# Controller.net
KiCad netlist of a schematic drawn in Altium Designer
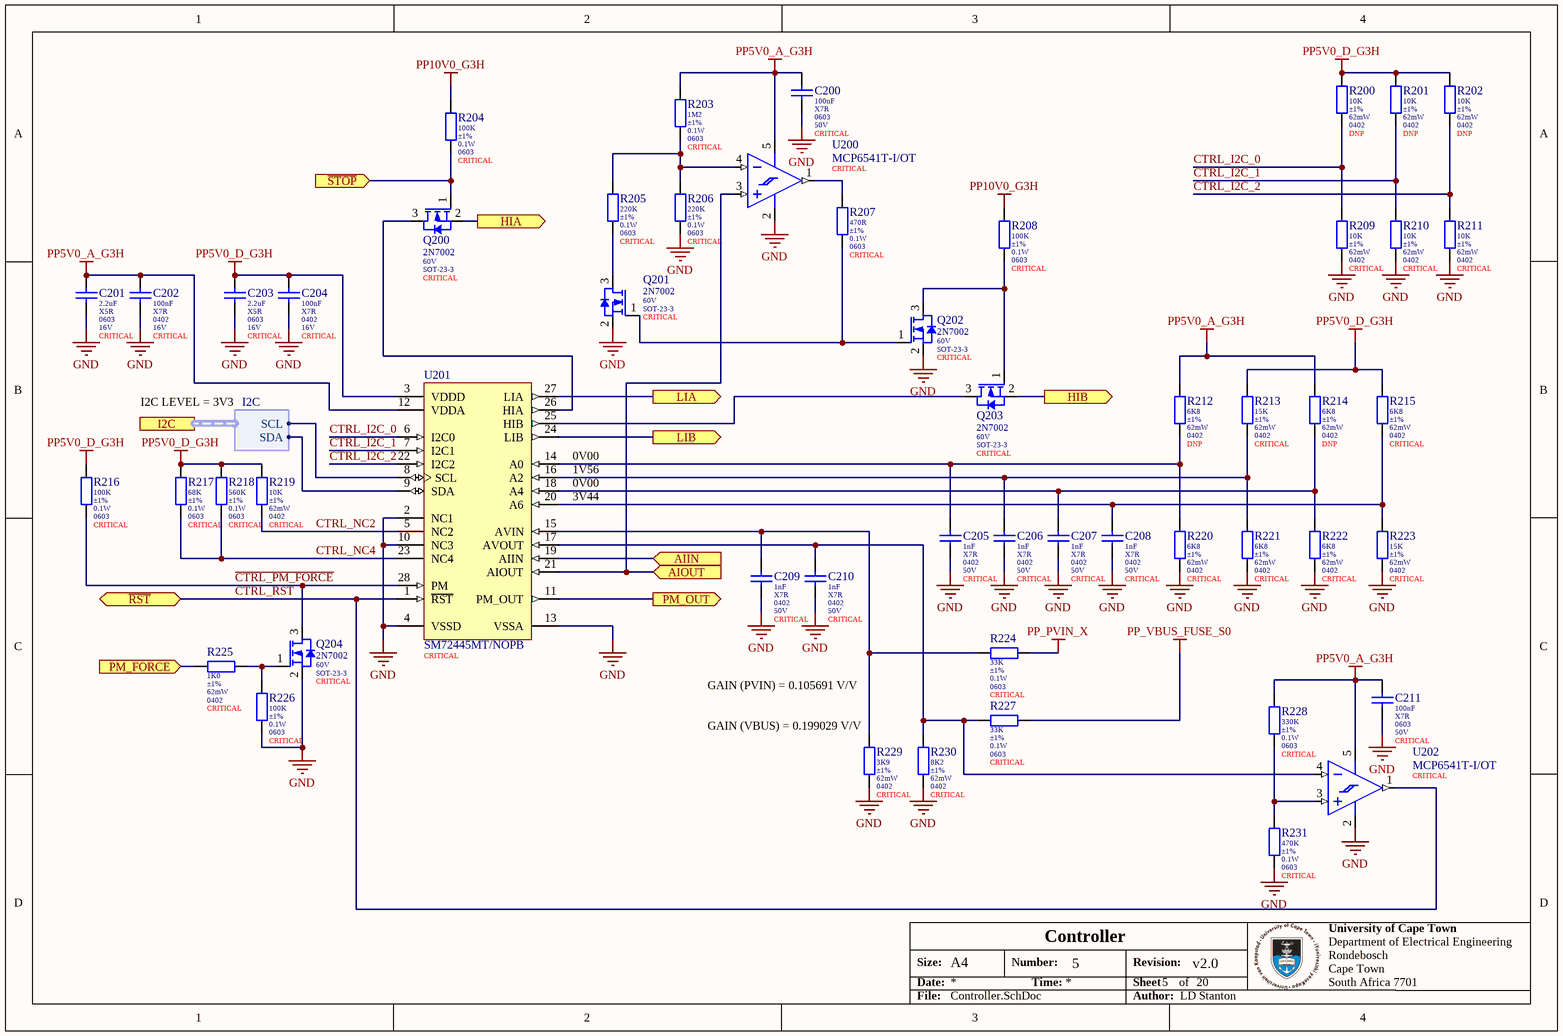
[diagram p0: Controller.SchDoc]

(export (version "E")
  (design (tool "Eeschema 10.0.6"))
  (components
    (comp (ref "C200")
      (value "100nF")
      (footprint "0603 (Yageo DA) B")
      (description "MLCC 100nF 50V 0603 X7R ±10%")
      (fields
        (field (name "DIELECTRIC") "X7R")
        (field (name "PACKAGE") "0603")
        (field (name "VOLTAGE") "50V")
        (field (name "POPULATE") "CRITICAL")
        (field (name "LCSC PART NUMBER") "C14663")
        (field (name "TOLERANCE") "±10%")
      )
      (libsource (lib "University of Cape Town") (part "Symbol"))
    )
    (comp (ref "C201")
      (value "2.2uF")
      (footprint "0603_080_8 (Samsung) B")
      (description "MLCC 2.2uF 0603 16V X5R ±10%")
      (fields
        (field (name "DIELECTRIC") "X5R")
        (field (name "PACKAGE") "0603")
        (field (name "VOLTAGE") "16V")
        (field (name "POPULATE") "CRITICAL")
        (field (name "MANUFACTURER") "Samsung")
        (field (name "LCSC PART NUMBER") "C23630")
      )
      (libsource (lib "University of Cape Town") (part "Symbol"))
    )
    (comp (ref "C202")
      (value "100nF")
      (footprint "0402_050_5 (Samsumg) B")
      (description "MLCC 100nF 0402 16V X7R ±10%")
      (fields
        (field (name "DIELECTRIC") "X7R")
        (field (name "PACKAGE") "0402")
        (field (name "VOLTAGE") "16V")
        (field (name "POPULATE") "CRITICAL")
        (field (name "TOLERANCE") "±10%")
        (field (name "LCSC PART NUMBER") "C1525")
      )
      (libsource (lib "University of Cape Town") (part "Symbol"))
    )
    (comp (ref "C203")
      (value "2.2uF")
      (footprint "0603_080_8 (Samsung) B")
      (description "MLCC 2.2uF 0603 16V X5R ±10%")
      (fields
        (field (name "DIELECTRIC") "X5R")
        (field (name "PACKAGE") "0603")
        (field (name "VOLTAGE") "16V")
        (field (name "POPULATE") "CRITICAL")
        (field (name "MANUFACTURER") "Samsung")
        (field (name "LCSC PART NUMBER") "C23630")
      )
      (libsource (lib "University of Cape Town") (part "Symbol"))
    )
    (comp (ref "C204")
      (value "100nF")
      (footprint "0402_050_5 (Samsumg) B")
      (description "MLCC 100nF 0402 16V X7R ±10%")
      (fields
        (field (name "DIELECTRIC") "X7R")
        (field (name "PACKAGE") "0402")
        (field (name "VOLTAGE") "16V")
        (field (name "POPULATE") "CRITICAL")
        (field (name "TOLERANCE") "±10%")
        (field (name "LCSC PART NUMBER") "C1525")
      )
      (libsource (lib "University of Cape Town") (part "Symbol"))
    )
    (comp (ref "C205")
      (value "1nF")
      (footprint "0402_050 (Guandong) B")
      (description "MLCC 1nF 0402 50V X7R ±10%")
      (fields
        (field (name "DIELECTRIC") "X7R")
        (field (name "PACKAGE") "0402")
        (field (name "VOLTAGE") "50V")
        (field (name "POPULATE") "CRITICAL")
        (field (name "LCSC PART NUMBER") "C1523")
        (field (name "MANUFACTURER") "Guandong")
      )
      (libsource (lib "University of Cape Town") (part "Symbol"))
    )
    (comp (ref "C206")
      (value "1nF")
      (footprint "0402_050 (Guandong) B")
      (description "MLCC 1nF 0402 50V X7R ±10%")
      (fields
        (field (name "DIELECTRIC") "X7R")
        (field (name "PACKAGE") "0402")
        (field (name "VOLTAGE") "50V")
        (field (name "POPULATE") "CRITICAL")
        (field (name "LCSC PART NUMBER") "C1523")
        (field (name "MANUFACTURER") "Guandong")
      )
      (libsource (lib "University of Cape Town") (part "Symbol"))
    )
    (comp (ref "C207")
      (value "1nF")
      (footprint "0402_050 (Guandong) B")
      (description "MLCC 1nF 0402 50V X7R ±10%")
      (fields
        (field (name "DIELECTRIC") "X7R")
        (field (name "PACKAGE") "0402")
        (field (name "VOLTAGE") "50V")
        (field (name "POPULATE") "CRITICAL")
        (field (name "LCSC PART NUMBER") "C1523")
        (field (name "MANUFACTURER") "Guandong")
      )
      (libsource (lib "University of Cape Town") (part "Symbol"))
    )
    (comp (ref "C208")
      (value "1nF")
      (footprint "0402_050 (Guandong) B")
      (description "MLCC 1nF 0402 50V X7R ±10%")
      (fields
        (field (name "DIELECTRIC") "X7R")
        (field (name "PACKAGE") "0402")
        (field (name "VOLTAGE") "50V")
        (field (name "POPULATE") "CRITICAL")
        (field (name "LCSC PART NUMBER") "C1523")
        (field (name "MANUFACTURER") "Guandong")
      )
      (libsource (lib "University of Cape Town") (part "Symbol"))
    )
    (comp (ref "C209")
      (value "1nF")
      (footprint "0402_050 (Guandong) B")
      (description "MLCC 1nF 0402 50V X7R ±10%")
      (fields
        (field (name "DIELECTRIC") "X7R")
        (field (name "PACKAGE") "0402")
        (field (name "VOLTAGE") "50V")
        (field (name "POPULATE") "CRITICAL")
        (field (name "LCSC PART NUMBER") "C1523")
        (field (name "MANUFACTURER") "Guandong")
      )
      (libsource (lib "University of Cape Town") (part "Symbol"))
    )
    (comp (ref "C210")
      (value "1nF")
      (footprint "0402_050 (Guandong) B")
      (description "MLCC 1nF 0402 50V X7R ±10%")
      (fields
        (field (name "DIELECTRIC") "X7R")
        (field (name "PACKAGE") "0402")
        (field (name "VOLTAGE") "50V")
        (field (name "POPULATE") "CRITICAL")
        (field (name "LCSC PART NUMBER") "C1523")
        (field (name "MANUFACTURER") "Guandong")
      )
      (libsource (lib "University of Cape Town") (part "Symbol"))
    )
    (comp (ref "C211")
      (value "100nF")
      (footprint "0603 (Yageo DA) B")
      (description "MLCC 100nF 50V 0603 X7R ±10%")
      (fields
        (field (name "DIELECTRIC") "X7R")
        (field (name "PACKAGE") "0603")
        (field (name "VOLTAGE") "50V")
        (field (name "POPULATE") "CRITICAL")
        (field (name "LCSC PART NUMBER") "C14663")
        (field (name "TOLERANCE") "±10%")
      )
      (libsource (lib "University of Cape Town") (part "Symbol"))
    )
    (comp (ref "Q200")
      (value "2N7002")
      (footprint "SOT-23-3 (2N7002) B")
      (description "Small Signal MOSFET, 500 mA, 60 V, N-Channel, Enhancement, JCET SOT-23-3")
      (fields
        (field (name "MAXIMUM DRAIN SOURCE VOLTAGE") "60V")
        (field (name "PACKAGE") "SOT-23-3")
        (field (name "PLACEMENT") "CRITICAL")
        (field (name "POWER") "0.225W")
        (field (name "LCSC PART NUMBER") "C8545")
      )
      (libsource (lib "University of Cape Town") (part "N Channel Transistor SOT-23-3"))
    )
    (comp (ref "Q201")
      (value "2N7002")
      (footprint "SOT-23-3 (2N7002) B")
      (description "Small Signal MOSFET, 500 mA, 60 V, N-Channel, Enhancement, JCET SOT-23-3")
      (fields
        (field (name "MAXIMUM DRAIN SOURCE VOLTAGE") "60V")
        (field (name "PACKAGE") "SOT-23-3")
        (field (name "PLACEMENT") "CRITICAL")
        (field (name "POWER") "0.225W")
        (field (name "LCSC PART NUMBER") "C8545")
      )
      (libsource (lib "University of Cape Town") (part "N Channel Transistor SOT-23-3"))
    )
    (comp (ref "Q202")
      (value "2N7002")
      (footprint "SOT-23-3 (2N7002) B")
      (description "Small Signal MOSFET, 500 mA, 60 V, N-Channel, Enhancement, JCET SOT-23-3")
      (fields
        (field (name "MAXIMUM DRAIN SOURCE VOLTAGE") "60V")
        (field (name "PACKAGE") "SOT-23-3")
        (field (name "PLACEMENT") "CRITICAL")
        (field (name "POWER") "0.225W")
        (field (name "LCSC PART NUMBER") "C8545")
      )
      (libsource (lib "University of Cape Town") (part "N Channel Transistor SOT-23-3"))
    )
    (comp (ref "Q203")
      (value "2N7002")
      (footprint "SOT-23-3 (2N7002) B")
      (description "Small Signal MOSFET, 500 mA, 60 V, N-Channel, Enhancement, JCET SOT-23-3")
      (fields
        (field (name "MAXIMUM DRAIN SOURCE VOLTAGE") "60V")
        (field (name "PACKAGE") "SOT-23-3")
        (field (name "PLACEMENT") "CRITICAL")
        (field (name "POWER") "0.225W")
        (field (name "LCSC PART NUMBER") "C8545")
      )
      (libsource (lib "University of Cape Town") (part "N Channel Transistor SOT-23-3"))
    )
    (comp (ref "Q204")
      (value "2N7002")
      (footprint "SOT-23-3 (2N7002) B")
      (description "Small Signal MOSFET, 500 mA, 60 V, N-Channel, Enhancement, JCET SOT-23-3")
      (fields
        (field (name "MAXIMUM DRAIN SOURCE VOLTAGE") "60V")
        (field (name "PACKAGE") "SOT-23-3")
        (field (name "PLACEMENT") "CRITICAL")
        (field (name "POWER") "0.225W")
        (field (name "LCSC PART NUMBER") "C8545")
      )
      (libsource (lib "University of Cape Town") (part "N Channel Transistor SOT-23-3"))
    )
    (comp (ref "R200")
      (value "10K")
      (footprint "0402 (Uniroyal) B")
      (description "Resistor 10K 0402 ±1% Thick Film Uniroyal")
      (fields
        (field (name "TOLERANCE") "±1%")
        (field (name "POWER") "62mW")
        (field (name "PACKAGE") "0402")
        (field (name "POPULATE") "DNP")
        (field (name "MANUFACTURER") "Uniroyal")
        (field (name "LCSC PART NUMBER") "C25744")
      )
      (libsource (lib "University of Cape Town") (part "Chip Resistor"))
    )
    (comp (ref "R201")
      (value "10K")
      (footprint "0402 (Uniroyal) B")
      (description "Resistor 10K 0402 ±1% Thick Film Uniroyal")
      (fields
        (field (name "TOLERANCE") "±1%")
        (field (name "POWER") "62mW")
        (field (name "PACKAGE") "0402")
        (field (name "POPULATE") "DNP")
        (field (name "MANUFACTURER") "Uniroyal")
        (field (name "LCSC PART NUMBER") "C25744")
      )
      (libsource (lib "University of Cape Town") (part "Chip Resistor"))
    )
    (comp (ref "R202")
      (value "10K")
      (footprint "0402 (Uniroyal) B")
      (description "Resistor 10K 0402 ±1% Thick Film Uniroyal")
      (fields
        (field (name "TOLERANCE") "±1%")
        (field (name "POWER") "62mW")
        (field (name "PACKAGE") "0402")
        (field (name "POPULATE") "DNP")
        (field (name "MANUFACTURER") "Uniroyal")
        (field (name "LCSC PART NUMBER") "C25744")
      )
      (libsource (lib "University of Cape Town") (part "Chip Resistor"))
    )
    (comp (ref "R203")
      (value "1M2")
      (footprint "0603 (Uniroyal) B")
      (description "Resistor 1M2 0603 ±1% Thick Film Uniroyal")
      (fields
        (field (name "TOLERANCE") "±1%")
        (field (name "POWER") "0.1W")
        (field (name "PACKAGE") "0603")
        (field (name "POPULATE") "CRITICAL")
        (field (name "MANUFACTURER") "Uniroyal")
        (field (name "LCSC PART NUMBER") "C13315")
      )
      (libsource (lib "University of Cape Town") (part "Chip Resistor"))
    )
    (comp (ref "R204")
      (value "100K")
      (footprint "0603 (Uniroyal) B")
      (description "Resistor 100K 0603 ±1% Thick Film Uniroyal")
      (fields
        (field (name "TOLERANCE") "±1%")
        (field (name "POWER") "0.1W")
        (field (name "PACKAGE") "0603")
        (field (name "POPULATE") "CRITICAL")
        (field (name "MANUFACTURER") "Uniroyal")
        (field (name "LCSC PART NUMBER") "C25803")
      )
      (libsource (lib "University of Cape Town") (part "Chip Resistor"))
    )
    (comp (ref "R205")
      (value "220K")
      (footprint "0603 (Uniroyal) B")
      (description "Resistor 220K 0603 ±1% Thick Film Uniroyal")
      (fields
        (field (name "TOLERANCE") "±1%")
        (field (name "POWER") "0.1W")
        (field (name "PACKAGE") "0603")
        (field (name "POPULATE") "CRITICAL")
        (field (name "MANUFACTURER") "Uniroyal")
        (field (name "LCSC PART NUMBER") "C22961")
      )
      (libsource (lib "University of Cape Town") (part "Chip Resistor"))
    )
    (comp (ref "R206")
      (value "220K")
      (footprint "0603 (Uniroyal) B")
      (description "Resistor 220K 0603 ±1% Thick Film Uniroyal")
      (fields
        (field (name "TOLERANCE") "±1%")
        (field (name "POWER") "0.1W")
        (field (name "PACKAGE") "0603")
        (field (name "POPULATE") "CRITICAL")
        (field (name "MANUFACTURER") "Uniroyal")
        (field (name "LCSC PART NUMBER") "C22961")
      )
      (libsource (lib "University of Cape Town") (part "Chip Resistor"))
    )
    (comp (ref "R207")
      (value "470R")
      (footprint "0603 (Uniroyal) B")
      (description "Resistor 470R 0603 ±5% Thick Film Uniroyal")
      (fields
        (field (name "TOLERANCE") "±1%")
        (field (name "POWER") "0.1W")
        (field (name "PACKAGE") "0603")
        (field (name "POPULATE") "CRITICAL")
        (field (name "MANUFACTURER") "Uniroyal")
        (field (name "LCSC PART NUMBER") "C23179")
      )
      (libsource (lib "University of Cape Town") (part "Chip Resistor"))
    )
    (comp (ref "R208")
      (value "100K")
      (footprint "0603 (Uniroyal) B")
      (description "Resistor 100K 0603 ±1% Thick Film Uniroyal")
      (fields
        (field (name "TOLERANCE") "±1%")
        (field (name "POWER") "0.1W")
        (field (name "PACKAGE") "0603")
        (field (name "POPULATE") "CRITICAL")
        (field (name "MANUFACTURER") "Uniroyal")
        (field (name "LCSC PART NUMBER") "C25803")
      )
      (libsource (lib "University of Cape Town") (part "Chip Resistor"))
    )
    (comp (ref "R209")
      (value "10K")
      (footprint "0402 (Uniroyal) B")
      (description "Resistor 10K 0402 ±1% Thick Film Uniroyal")
      (fields
        (field (name "TOLERANCE") "±1%")
        (field (name "POWER") "62mW")
        (field (name "PACKAGE") "0402")
        (field (name "POPULATE") "CRITICAL")
        (field (name "MANUFACTURER") "Uniroyal")
        (field (name "LCSC PART NUMBER") "C25744")
      )
      (libsource (lib "University of Cape Town") (part "Chip Resistor"))
    )
    (comp (ref "R210")
      (value "10K")
      (footprint "0402 (Uniroyal) B")
      (description "Resistor 10K 0402 ±1% Thick Film Uniroyal")
      (fields
        (field (name "TOLERANCE") "±1%")
        (field (name "POWER") "62mW")
        (field (name "PACKAGE") "0402")
        (field (name "POPULATE") "CRITICAL")
        (field (name "MANUFACTURER") "Uniroyal")
        (field (name "LCSC PART NUMBER") "C25744")
      )
      (libsource (lib "University of Cape Town") (part "Chip Resistor"))
    )
    (comp (ref "R211")
      (value "10K")
      (footprint "0402 (Uniroyal) B")
      (description "Resistor 10K 0402 ±1% Thick Film Uniroyal")
      (fields
        (field (name "TOLERANCE") "±1%")
        (field (name "POWER") "62mW")
        (field (name "PACKAGE") "0402")
        (field (name "POPULATE") "CRITICAL")
        (field (name "MANUFACTURER") "Uniroyal")
        (field (name "LCSC PART NUMBER") "C25744")
      )
      (libsource (lib "University of Cape Town") (part "Chip Resistor"))
    )
    (comp (ref "R212")
      (value "6K8")
      (footprint "0402 (Uniroyal) B")
      (description "Resistor 6K8 0402 ±1% Thick Film Uniroyal")
      (fields
        (field (name "TOLERANCE") "±1%")
        (field (name "POWER") "62mW")
        (field (name "PACKAGE") "0402")
        (field (name "POPULATE") "DNP")
        (field (name "MANUFACTURER") "Uniroyal")
        (field (name "LCSC PART NUMBER") "C25917")
      )
      (libsource (lib "University of Cape Town") (part "Chip Resistor"))
    )
    (comp (ref "R213")
      (value "15K")
      (footprint "0402 (Uniroyal) B")
      (description "Resistor 15K 0402 ±1% Thick Film Uniroyal")
      (fields
        (field (name "TOLERANCE") "±1%")
        (field (name "POWER") "62mW")
        (field (name "PACKAGE") "0402")
        (field (name "POPULATE") "CRITICAL")
        (field (name "MANUFACTURER") "Uniroyal")
        (field (name "LCSC PART NUMBER") "C25756")
      )
      (libsource (lib "University of Cape Town") (part "Chip Resistor"))
    )
    (comp (ref "R214")
      (value "6K8")
      (footprint "0402 (Uniroyal) B")
      (description "Resistor 6K8 0402 ±1% Thick Film Uniroyal")
      (fields
        (field (name "TOLERANCE") "±1%")
        (field (name "POWER") "62mW")
        (field (name "PACKAGE") "0402")
        (field (name "POPULATE") "DNP")
        (field (name "MANUFACTURER") "Uniroyal")
        (field (name "LCSC PART NUMBER") "C25917")
      )
      (libsource (lib "University of Cape Town") (part "Chip Resistor"))
    )
    (comp (ref "R215")
      (value "6K8")
      (footprint "0402 (Uniroyal) B")
      (description "Resistor 6K8 0402 ±1% Thick Film Uniroyal")
      (fields
        (field (name "TOLERANCE") "±1%")
        (field (name "POWER") "62mW")
        (field (name "PACKAGE") "0402")
        (field (name "POPULATE") "CRITICAL")
        (field (name "MANUFACTURER") "Uniroyal")
        (field (name "LCSC PART NUMBER") "C25917")
      )
      (libsource (lib "University of Cape Town") (part "Chip Resistor"))
    )
    (comp (ref "R216")
      (value "100K")
      (footprint "0603 (Uniroyal) B")
      (description "Resistor 100K 0603 ±1% Thick Film Uniroyal")
      (fields
        (field (name "TOLERANCE") "±1%")
        (field (name "POWER") "0.1W")
        (field (name "PACKAGE") "0603")
        (field (name "POPULATE") "CRITICAL")
        (field (name "MANUFACTURER") "Uniroyal")
        (field (name "LCSC PART NUMBER") "C25803")
      )
      (libsource (lib "University of Cape Town") (part "Chip Resistor"))
    )
    (comp (ref "R217")
      (value "68K")
      (footprint "0603 (Uniroyal) B")
      (description "Resistor 68K 0603 ±1% Thick Film Uniroyal")
      (fields
        (field (name "TOLERANCE") "±1%")
        (field (name "POWER") "0.1W")
        (field (name "PACKAGE") "0603")
        (field (name "POPULATE") "CRITICAL")
        (field (name "LCSC PART NUMBER") "C23231")
        (field (name "MANUFACTURER") "Uniroyal")
      )
      (libsource (lib "University of Cape Town") (part "Chip Resistor"))
    )
    (comp (ref "R218")
      (value "560K")
      (footprint "0603 (Uniroyal) B")
      (description "Resistor 560K 0603 ±1% Thick Film Uniroyal")
      (fields
        (field (name "TOLERANCE") "±1%")
        (field (name "POWER") "0.1W")
        (field (name "PACKAGE") "0603")
        (field (name "POPULATE") "CRITICAL")
        (field (name "LCSC PART NUMBER") "C23203")
        (field (name "MANUFACTURER") "Uniroyal")
      )
      (libsource (lib "University of Cape Town") (part "Chip Resistor"))
    )
    (comp (ref "R219")
      (value "10K")
      (footprint "0402 (Uniroyal) B")
      (description "Resistor 10K 0402 ±1% Thick Film Uniroyal")
      (fields
        (field (name "TOLERANCE") "±1%")
        (field (name "POWER") "62mW")
        (field (name "PACKAGE") "0402")
        (field (name "POPULATE") "CRITICAL")
        (field (name "LCSC PART NUMBER") "C25744")
        (field (name "MANUFACTURER") "Uniroyal")
      )
      (libsource (lib "University of Cape Town") (part "Chip Resistor"))
    )
    (comp (ref "R220")
      (value "6K8")
      (footprint "0402 (Uniroyal) B")
      (description "Resistor 6K8 0402 ±1% Thick Film Uniroyal")
      (fields
        (field (name "TOLERANCE") "±1%")
        (field (name "POWER") "62mW")
        (field (name "PACKAGE") "0402")
        (field (name "POPULATE") "CRITICAL")
        (field (name "MANUFACTURER") "Uniroyal")
        (field (name "LCSC PART NUMBER") "C25917")
      )
      (libsource (lib "University of Cape Town") (part "Chip Resistor"))
    )
    (comp (ref "R221")
      (value "6K8")
      (footprint "0402 (Uniroyal) B")
      (description "Resistor 6K8 0402 ±1% Thick Film Uniroyal")
      (fields
        (field (name "TOLERANCE") "±1%")
        (field (name "POWER") "62mW")
        (field (name "PACKAGE") "0402")
        (field (name "POPULATE") "CRITICAL")
        (field (name "MANUFACTURER") "Uniroyal")
        (field (name "LCSC PART NUMBER") "C25917")
      )
      (libsource (lib "University of Cape Town") (part "Chip Resistor"))
    )
    (comp (ref "R222")
      (value "6K8")
      (footprint "0402 (Uniroyal) B")
      (description "Resistor 6K8 0402 ±1% Thick Film Uniroyal")
      (fields
        (field (name "TOLERANCE") "±1%")
        (field (name "POWER") "62mW")
        (field (name "PACKAGE") "0402")
        (field (name "POPULATE") "CRITICAL")
        (field (name "MANUFACTURER") "Uniroyal")
        (field (name "LCSC PART NUMBER") "C25917")
      )
      (libsource (lib "University of Cape Town") (part "Chip Resistor"))
    )
    (comp (ref "R223")
      (value "15K")
      (footprint "0402 (Uniroyal) B")
      (description "Resistor 15K 0402 ±1% Thick Film Uniroyal")
      (fields
        (field (name "TOLERANCE") "±1%")
        (field (name "POWER") "62mW")
        (field (name "PACKAGE") "0402")
        (field (name "POPULATE") "CRITICAL")
        (field (name "MANUFACTURER") "Uniroyal")
        (field (name "LCSC PART NUMBER") "C25756")
      )
      (libsource (lib "University of Cape Town") (part "Chip Resistor"))
    )
    (comp (ref "R224")
      (value "33K")
      (footprint "0603 (Uniroyal) B")
      (description "Resistor 33K 0603 ±1% Thick Film Uniroyal")
      (fields
        (field (name "TOLERANCE") "±1%")
        (field (name "POWER") "0.1W")
        (field (name "PACKAGE") "0603")
        (field (name "POPULATE") "CRITICAL")
        (field (name "MANUFACTURER") "Uniroyal")
        (field (name "LCSC PART NUMBER") "C4216")
      )
      (libsource (lib "University of Cape Town") (part "Chip Resistor"))
    )
    (comp (ref "R225")
      (value "1K0")
      (footprint "0402 (Uniroyal) B")
      (description "Resistor 1K0 0402 ±1% Thick Film Uniroyal")
      (fields
        (field (name "TOLERANCE") "±1%")
        (field (name "POWER") "62mW")
        (field (name "PACKAGE") "0402")
        (field (name "POPULATE") "CRITICAL")
        (field (name "MANUFACTURER") "Uniroyal")
        (field (name "LCSC PART NUMBER") "C11702")
      )
      (libsource (lib "University of Cape Town") (part "Chip Resistor"))
    )
    (comp (ref "R226")
      (value "100K")
      (footprint "0603 (Uniroyal) B")
      (description "Resistor 100K 0603 ±1% Thick Film Uniroyal")
      (fields
        (field (name "TOLERANCE") "±1%")
        (field (name "POWER") "0.1W")
        (field (name "PACKAGE") "0603")
        (field (name "POPULATE") "CRITICAL")
        (field (name "MANUFACTURER") "Uniroyal")
        (field (name "LCSC PART NUMBER") "C25803")
      )
      (libsource (lib "University of Cape Town") (part "Chip Resistor"))
    )
    (comp (ref "R227")
      (value "33K")
      (footprint "0603 (Uniroyal) B")
      (description "Resistor 33K 0603 ±1% Thick Film Uniroyal")
      (fields
        (field (name "TOLERANCE") "±1%")
        (field (name "POWER") "0.1W")
        (field (name "PACKAGE") "0603")
        (field (name "POPULATE") "CRITICAL")
        (field (name "MANUFACTURER") "Uniroyal")
        (field (name "LCSC PART NUMBER") "C4216")
      )
      (libsource (lib "University of Cape Town") (part "Chip Resistor"))
    )
    (comp (ref "R228")
      (value "330K")
      (footprint "0603 (Uniroyal) B")
      (description "Resistor 330K 0603 ±1% Thick Film Uniroyal")
      (fields
        (field (name "TOLERANCE") "±1%")
        (field (name "POWER") "0.1W")
        (field (name "PACKAGE") "0603")
        (field (name "POPULATE") "CRITICAL")
        (field (name "MANUFACTURER") "Uniroyal")
        (field (name "LCSC PART NUMBER") "C23137")
      )
      (libsource (lib "University of Cape Town") (part "Chip Resistor"))
    )
    (comp (ref "R229")
      (value "3K9")
      (footprint "0402 (Uniroyal) B")
      (description "Resistor 3K9 0402 ±1% Thick Film Uniroyal")
      (fields
        (field (name "TOLERANCE") "±1%")
        (field (name "POWER") "62mW")
        (field (name "PACKAGE") "0402")
        (field (name "POPULATE") "CRITICAL")
        (field (name "MANUFACTURER") "Uniroyal")
        (field (name "LCSC PART NUMBER") "C51721")
      )
      (libsource (lib "University of Cape Town") (part "Chip Resistor"))
    )
    (comp (ref "R230")
      (value "8K2")
      (footprint "0402 (Uniroyal) B")
      (description "Resistor 8K2 0402 ±1% Thick Film Uniroyal")
      (fields
        (field (name "TOLERANCE") "±1%")
        (field (name "POWER") "62mW")
        (field (name "PACKAGE") "0402")
        (field (name "POPULATE") "CRITICAL")
        (field (name "LCSC PART NUMBER") "C25924")
        (field (name "MANUFACTURER") "Uniroyal")
      )
      (libsource (lib "University of Cape Town") (part "Chip Resistor"))
    )
    (comp (ref "R231")
      (value "470K")
      (footprint "0603 (Uniroyal) B")
      (description "Resistor 470K 0603 ±1% Thick Film Uniroyal")
      (fields
        (field (name "TOLERANCE") "±1%")
        (field (name "POWER") "0.1W")
        (field (name "PACKAGE") "0603")
        (field (name "POPULATE") "CRITICAL")
        (field (name "LCSC PART NUMBER") "C23178")
        (field (name "MANUFACTURER") "Uniroyal")
      )
      (libsource (lib "University of Cape Town") (part "Chip Resistor"))
    )
    (comp (ref "U200")
      (value "MCP6541T-I/OT")
      (footprint "SOT-23-5 (MCP75x) B")
      (description "Comparator, Push-Pull, 1V6-5V5, 600nA,  SOT-23-5")
      (fields (field (name "PLACEMENT") "CRITICAL") (field (name "LCSC PART NUMBER") "C80839"))
      (libsource (lib "University of Cape Town") (part "MCP7541"))
    )
    (comp (ref "U201")
      (value "SM72445MT/NOPB")
      (footprint "PW0028A_N")
      (description "Texas Instruments MPPT Photovoltaic Cell Controller, 220kHz, TSSOP-28")
      (fields (field (name "PLACEMENT") "CRITICAL"))
      (libsource (lib "University of Cape Town") (part "IN-MPPT-SM72442-IL28"))
    )
    (comp (ref "U202")
      (value "MCP6541T-I/OT")
      (footprint "SOT-23-5 (MCP75x) B")
      (description "Comparator, Push-Pull, 1V6-5V5, 600nA,  SOT-23-5")
      (fields (field (name "PLACEMENT") "CRITICAL") (field (name "LCSC PART NUMBER") "C80839"))
      (libsource (lib "University of Cape Town") (part "MCP7541"))
    )
  )
  (nets
    (net (code "2") (name "/AIIN") (class "Default")
      (node (ref "U201") (pin "19") (pinfunction "AIIN_19") (pintype "input"))
    )
    (net (code "3") (name "/AIOUT") (class "Default")
      (node (ref "U200") (pin "3") (pinfunction "VIN+_3") (pintype "input"))
      (node (ref "U201") (pin "21") (pinfunction "AIOUT_21") (pintype "input"))
    )
    (net (code "4") (name "/CTRL_I2C_0") (class "Default")
      (node (ref "R200") (pin "2") (pinfunction "2_2") (pintype "passive"))
      (node (ref "R209") (pin "1") (pinfunction "1_1") (pintype "passive"))
      (node (ref "U201") (pin "6") (pinfunction "I2C0_6") (pintype "input"))
    )
    (net (code "5") (name "/CTRL_I2C_1") (class "Default")
      (node (ref "R201") (pin "2") (pinfunction "2_2") (pintype "passive"))
      (node (ref "R210") (pin "1") (pinfunction "1_1") (pintype "passive"))
      (node (ref "U201") (pin "7") (pinfunction "I2C1_7") (pintype "input"))
    )
    (net (code "6") (name "/CTRL_I2C_2") (class "Default")
      (node (ref "R202") (pin "2") (pinfunction "2_2") (pintype "passive"))
      (node (ref "R211") (pin "1") (pinfunction "1_1") (pintype "passive"))
      (node (ref "U201") (pin "22") (pinfunction "I2C2_22") (pintype "input"))
    )
    (net (code "7") (name "/CTRL_NC2") (class "Default")
      (node (ref "R219") (pin "1") (pinfunction "1_1") (pintype "passive"))
      (node (ref "U201") (pin "5") (pinfunction "NC2_5") (pintype "passive"))
    )
    (net (code "8") (name "/CTRL_NC4") (class "Default")
      (node (ref "R217") (pin "2") (pinfunction "2_2") (pintype "passive"))
      (node (ref "R218") (pin "2") (pinfunction "2_2") (pintype "passive"))
      (node (ref "U201") (pin "23") (pinfunction "NC4_23") (pintype "passive"))
    )
    (net (code "9") (name "/CTRL_PM_FORCE") (class "Default")
      (node (ref "Q204") (pin "3") (pinfunction "D_3") (pintype "passive"))
      (node (ref "R216") (pin "2") (pinfunction "2_2") (pintype "passive"))
      (node (ref "U201") (pin "28") (pinfunction "PM_28") (pintype "input"))
    )
    (net (code "10") (name "/CTRL_RST") (class "Default")
      (node (ref "U201") (pin "1") (pinfunction "~{RST}_1") (pintype "input"))
      (node (ref "U202") (pin "1") (pinfunction "OUT_1") (pintype "output"))
    )
    (net (code "11") (name "/HIA") (class "Default")
      (node (ref "Q200") (pin "2") (pinfunction "S_2") (pintype "passive"))
    )
    (net (code "12") (name "/HIB") (class "Default")
      (node (ref "Q203") (pin "2") (pinfunction "S_2") (pintype "passive"))
    )
    (net (code "13") (name "/LIA") (class "Default")
      (node (ref "U201") (pin "27") (pinfunction "LIA_27") (pintype "output"))
    )
    (net (code "14") (name "/LIB") (class "Default")
      (node (ref "U201") (pin "24") (pinfunction "LIB_24") (pintype "output"))
    )
    (net (code "15") (name "/PM_FORCE") (class "Default")
      (node (ref "R225") (pin "1") (pinfunction "1_1") (pintype "passive"))
    )
    (net (code "16") (name "/PM_OUT") (class "Default")
      (node (ref "U201") (pin "11") (pinfunction "PM_OUT_11") (pintype "output"))
    )
    (net (code "17") (name "/SCL") (class "Default")
      (node (ref "U201") (pin "8") (pinfunction "SCL_8") (pintype "bidirectional"))
    )
    (net (code "18") (name "/SDA") (class "Default")
      (node (ref "U201") (pin "9") (pinfunction "SDA_9") (pintype "bidirectional"))
    )
    (net (code "19") (name "/STOP") (class "Default")
      (node (ref "Q200") (pin "1") (pinfunction "G_1") (pintype "passive"))
      (node (ref "R204") (pin "2") (pinfunction "2_2") (pintype "passive"))
    )
    (net (code "21") (name "GND") (class "Default")
      (node (ref "C200") (pin "2") (pinfunction "2_2") (pintype "passive"))
      (node (ref "C201") (pin "2") (pinfunction "2_2") (pintype "passive"))
      (node (ref "C202") (pin "2") (pinfunction "2_2") (pintype "passive"))
      (node (ref "C203") (pin "2") (pinfunction "2_2") (pintype "passive"))
      (node (ref "C204") (pin "2") (pinfunction "2_2") (pintype "passive"))
      (node (ref "C205") (pin "2") (pinfunction "2_2") (pintype "passive"))
      (node (ref "C206") (pin "2") (pinfunction "2_2") (pintype "passive"))
      (node (ref "C207") (pin "2") (pinfunction "2_2") (pintype "passive"))
      (node (ref "C208") (pin "2") (pinfunction "2_2") (pintype "passive"))
      (node (ref "C209") (pin "2") (pinfunction "2_2") (pintype "passive"))
      (node (ref "C210") (pin "2") (pinfunction "2_2") (pintype "passive"))
      (node (ref "C211") (pin "2") (pinfunction "2_2") (pintype "passive"))
      (node (ref "Q201") (pin "2") (pinfunction "S_2") (pintype "passive"))
      (node (ref "Q202") (pin "2") (pinfunction "S_2") (pintype "passive"))
      (node (ref "Q204") (pin "2") (pinfunction "S_2") (pintype "passive"))
      (node (ref "R206") (pin "2") (pinfunction "2_2") (pintype "passive"))
      (node (ref "R209") (pin "2") (pinfunction "2_2") (pintype "passive"))
      (node (ref "R210") (pin "2") (pinfunction "2_2") (pintype "passive"))
      (node (ref "R211") (pin "2") (pinfunction "2_2") (pintype "passive"))
      (node (ref "R220") (pin "2") (pinfunction "2_2") (pintype "passive"))
      (node (ref "R221") (pin "2") (pinfunction "2_2") (pintype "passive"))
      (node (ref "R222") (pin "2") (pinfunction "2_2") (pintype "passive"))
      (node (ref "R223") (pin "2") (pinfunction "2_2") (pintype "passive"))
      (node (ref "R226") (pin "2") (pinfunction "2_2") (pintype "passive"))
      (node (ref "R229") (pin "2") (pinfunction "2_2") (pintype "passive"))
      (node (ref "R230") (pin "2") (pinfunction "2_2") (pintype "passive"))
      (node (ref "R231") (pin "2") (pinfunction "2_2") (pintype "passive"))
      (node (ref "U200") (pin "2") (pinfunction "VSS_2") (pintype "power_in"))
      (node (ref "U201") (pin "10") (pinfunction "NC3_10") (pintype "passive"))
      (node (ref "U201") (pin "13") (pinfunction "VSSA_13") (pintype "power_in"))
      (node (ref "U201") (pin "2") (pinfunction "NC1_2") (pintype "passive"))
      (node (ref "U201") (pin "4") (pinfunction "VSSD_4") (pintype "power_in"))
      (node (ref "U202") (pin "2") (pinfunction "VSS_2") (pintype "power_in"))
    )
    (net (code "22") (name "Net-(Q200-D)") (class "Default")
      (node (ref "Q200") (pin "3") (pinfunction "D_3") (pintype "passive"))
      (node (ref "U201") (pin "26") (pinfunction "HIA_26") (pintype "output"))
    )
    (net (code "23") (name "Net-(Q201-D)") (class "Default")
      (node (ref "Q201") (pin "3") (pinfunction "D_3") (pintype "passive"))
      (node (ref "R205") (pin "2") (pinfunction "2_2") (pintype "passive"))
    )
    (net (code "24") (name "Net-(Q201-G)") (class "Default")
      (node (ref "Q201") (pin "1") (pinfunction "G_1") (pintype "passive"))
      (node (ref "Q202") (pin "1") (pinfunction "G_1") (pintype "passive"))
      (node (ref "R207") (pin "1") (pinfunction "1_1") (pintype "passive"))
    )
    (net (code "25") (name "Net-(Q202-D)") (class "Default")
      (node (ref "Q202") (pin "3") (pinfunction "D_3") (pintype "passive"))
      (node (ref "Q203") (pin "1") (pinfunction "G_1") (pintype "passive"))
      (node (ref "R208") (pin "2") (pinfunction "2_2") (pintype "passive"))
    )
    (net (code "26") (name "Net-(Q203-D)") (class "Default")
      (node (ref "Q203") (pin "3") (pinfunction "D_3") (pintype "passive"))
      (node (ref "U201") (pin "25") (pinfunction "HIB_25") (pintype "output"))
    )
    (net (code "27") (name "Net-(Q204-G)") (class "Default")
      (node (ref "Q204") (pin "1") (pinfunction "G_1") (pintype "passive"))
      (node (ref "R225") (pin "2") (pinfunction "2_2") (pintype "passive"))
      (node (ref "R226") (pin "1") (pinfunction "1_1") (pintype "passive"))
    )
    (net (code "28") (name "Net-(U200-OUT)") (class "Default")
      (node (ref "R207") (pin "2") (pinfunction "2_2") (pintype "passive"))
      (node (ref "U200") (pin "1") (pinfunction "OUT_1") (pintype "output"))
    )
    (net (code "29") (name "Net-(U200-VIN-)") (class "Default")
      (node (ref "R203") (pin "2") (pinfunction "2_2") (pintype "passive"))
      (node (ref "R205") (pin "1") (pinfunction "1_1") (pintype "passive"))
      (node (ref "R206") (pin "1") (pinfunction "1_1") (pintype "passive"))
      (node (ref "U200") (pin "4") (pinfunction "VIN-_4") (pintype "input"))
    )
    (net (code "30") (name "Net-(U201-A0)") (class "Default")
      (node (ref "C205") (pin "1") (pinfunction "1_1") (pintype "passive"))
      (node (ref "R212") (pin "2") (pinfunction "2_2") (pintype "passive"))
      (node (ref "R220") (pin "1") (pinfunction "1_1") (pintype "passive"))
      (node (ref "U201") (pin "14") (pinfunction "A0_14") (pintype "input"))
    )
    (net (code "31") (name "Net-(U201-A2)") (class "Default")
      (node (ref "C206") (pin "1") (pinfunction "1_1") (pintype "passive"))
      (node (ref "R213") (pin "2") (pinfunction "2_2") (pintype "passive"))
      (node (ref "R221") (pin "1") (pinfunction "1_1") (pintype "passive"))
      (node (ref "U201") (pin "16") (pinfunction "A2_16") (pintype "input"))
    )
    (net (code "32") (name "Net-(U201-A4)") (class "Default")
      (node (ref "C207") (pin "1") (pinfunction "1_1") (pintype "passive"))
      (node (ref "R214") (pin "2") (pinfunction "2_2") (pintype "passive"))
      (node (ref "R222") (pin "1") (pinfunction "1_1") (pintype "passive"))
      (node (ref "U201") (pin "18") (pinfunction "A4_18") (pintype "input"))
    )
    (net (code "33") (name "Net-(U201-A6)") (class "Default")
      (node (ref "C208") (pin "1") (pinfunction "1_1") (pintype "passive"))
      (node (ref "R215") (pin "2") (pinfunction "2_2") (pintype "passive"))
      (node (ref "R223") (pin "1") (pinfunction "1_1") (pintype "passive"))
      (node (ref "U201") (pin "20") (pinfunction "A6_20") (pintype "input"))
    )
    (net (code "34") (name "Net-(U201-AVIN)") (class "Default")
      (node (ref "C209") (pin "1") (pinfunction "1_1") (pintype "passive"))
      (node (ref "R224") (pin "1") (pinfunction "1_1") (pintype "passive"))
      (node (ref "R229") (pin "1") (pinfunction "1_1") (pintype "passive"))
      (node (ref "U201") (pin "15") (pinfunction "AVIN_15") (pintype "input"))
    )
    (net (code "35") (name "Net-(U201-AVOUT)") (class "Default")
      (node (ref "C210") (pin "1") (pinfunction "1_1") (pintype "passive"))
      (node (ref "R227") (pin "1") (pinfunction "1_1") (pintype "passive"))
      (node (ref "R230") (pin "1") (pinfunction "1_1") (pintype "passive"))
      (node (ref "U201") (pin "17") (pinfunction "AVOUT_17") (pintype "input"))
      (node (ref "U202") (pin "4") (pinfunction "VIN-_4") (pintype "input"))
    )
    (net (code "36") (name "Net-(U202-VIN+)") (class "Default")
      (node (ref "R228") (pin "2") (pinfunction "2_2") (pintype "passive"))
      (node (ref "R231") (pin "1") (pinfunction "1_1") (pintype "passive"))
      (node (ref "U202") (pin "3") (pinfunction "VIN+_3") (pintype "input"))
    )
    (net (code "37") (name "PP5V0_A_G3H") (class "Default")
      (node (ref "C200") (pin "1") (pinfunction "1_1") (pintype "passive"))
      (node (ref "C201") (pin "1") (pinfunction "1_1") (pintype "passive"))
      (node (ref "C202") (pin "1") (pinfunction "1_1") (pintype "passive"))
      (node (ref "C211") (pin "1") (pinfunction "1_1") (pintype "passive"))
      (node (ref "R203") (pin "1") (pinfunction "1_1") (pintype "passive"))
      (node (ref "R212") (pin "1") (pinfunction "1_1") (pintype "passive"))
      (node (ref "R214") (pin "1") (pinfunction "1_1") (pintype "passive"))
      (node (ref "R228") (pin "1") (pinfunction "1_1") (pintype "passive"))
      (node (ref "U200") (pin "5") (pinfunction "VDD_5") (pintype "power_in"))
      (node (ref "U201") (pin "12") (pinfunction "VDDA_12") (pintype "power_in"))
      (node (ref "U202") (pin "5") (pinfunction "VDD_5") (pintype "power_in"))
    )
    (net (code "38") (name "PP5V0_D_G3H") (class "Default")
      (node (ref "C203") (pin "1") (pinfunction "1_1") (pintype "passive"))
      (node (ref "C204") (pin "1") (pinfunction "1_1") (pintype "passive"))
      (node (ref "R200") (pin "1") (pinfunction "1_1") (pintype "passive"))
      (node (ref "R201") (pin "1") (pinfunction "1_1") (pintype "passive"))
      (node (ref "R202") (pin "1") (pinfunction "1_1") (pintype "passive"))
      (node (ref "R213") (pin "1") (pinfunction "1_1") (pintype "passive"))
      (node (ref "R215") (pin "1") (pinfunction "1_1") (pintype "passive"))
      (node (ref "R216") (pin "1") (pinfunction "1_1") (pintype "passive"))
      (node (ref "R217") (pin "1") (pinfunction "1_1") (pintype "passive"))
      (node (ref "R218") (pin "1") (pinfunction "1_1") (pintype "passive"))
      (node (ref "R219") (pin "2") (pinfunction "2_2") (pintype "passive"))
      (node (ref "U201") (pin "3") (pinfunction "VDDD_3") (pintype "power_in"))
    )
    (net (code "39") (name "PP10V0_G3H") (class "Default")
      (node (ref "R204") (pin "1") (pinfunction "1_1") (pintype "passive"))
      (node (ref "R208") (pin "1") (pinfunction "1_1") (pintype "passive"))
    )
    (net (code "40") (name "PP_PVIN_X") (class "Default")
      (node (ref "R224") (pin "2") (pinfunction "2_2") (pintype "passive"))
    )
    (net (code "41") (name "PP_VBUS_FUSE_S0") (class "Default")
      (node (ref "R227") (pin "2") (pinfunction "2_2") (pintype "passive"))
    )
  )
)
